# SPI_SensorShield.net
KiCad netlist of a schematic drawn in EAGLE
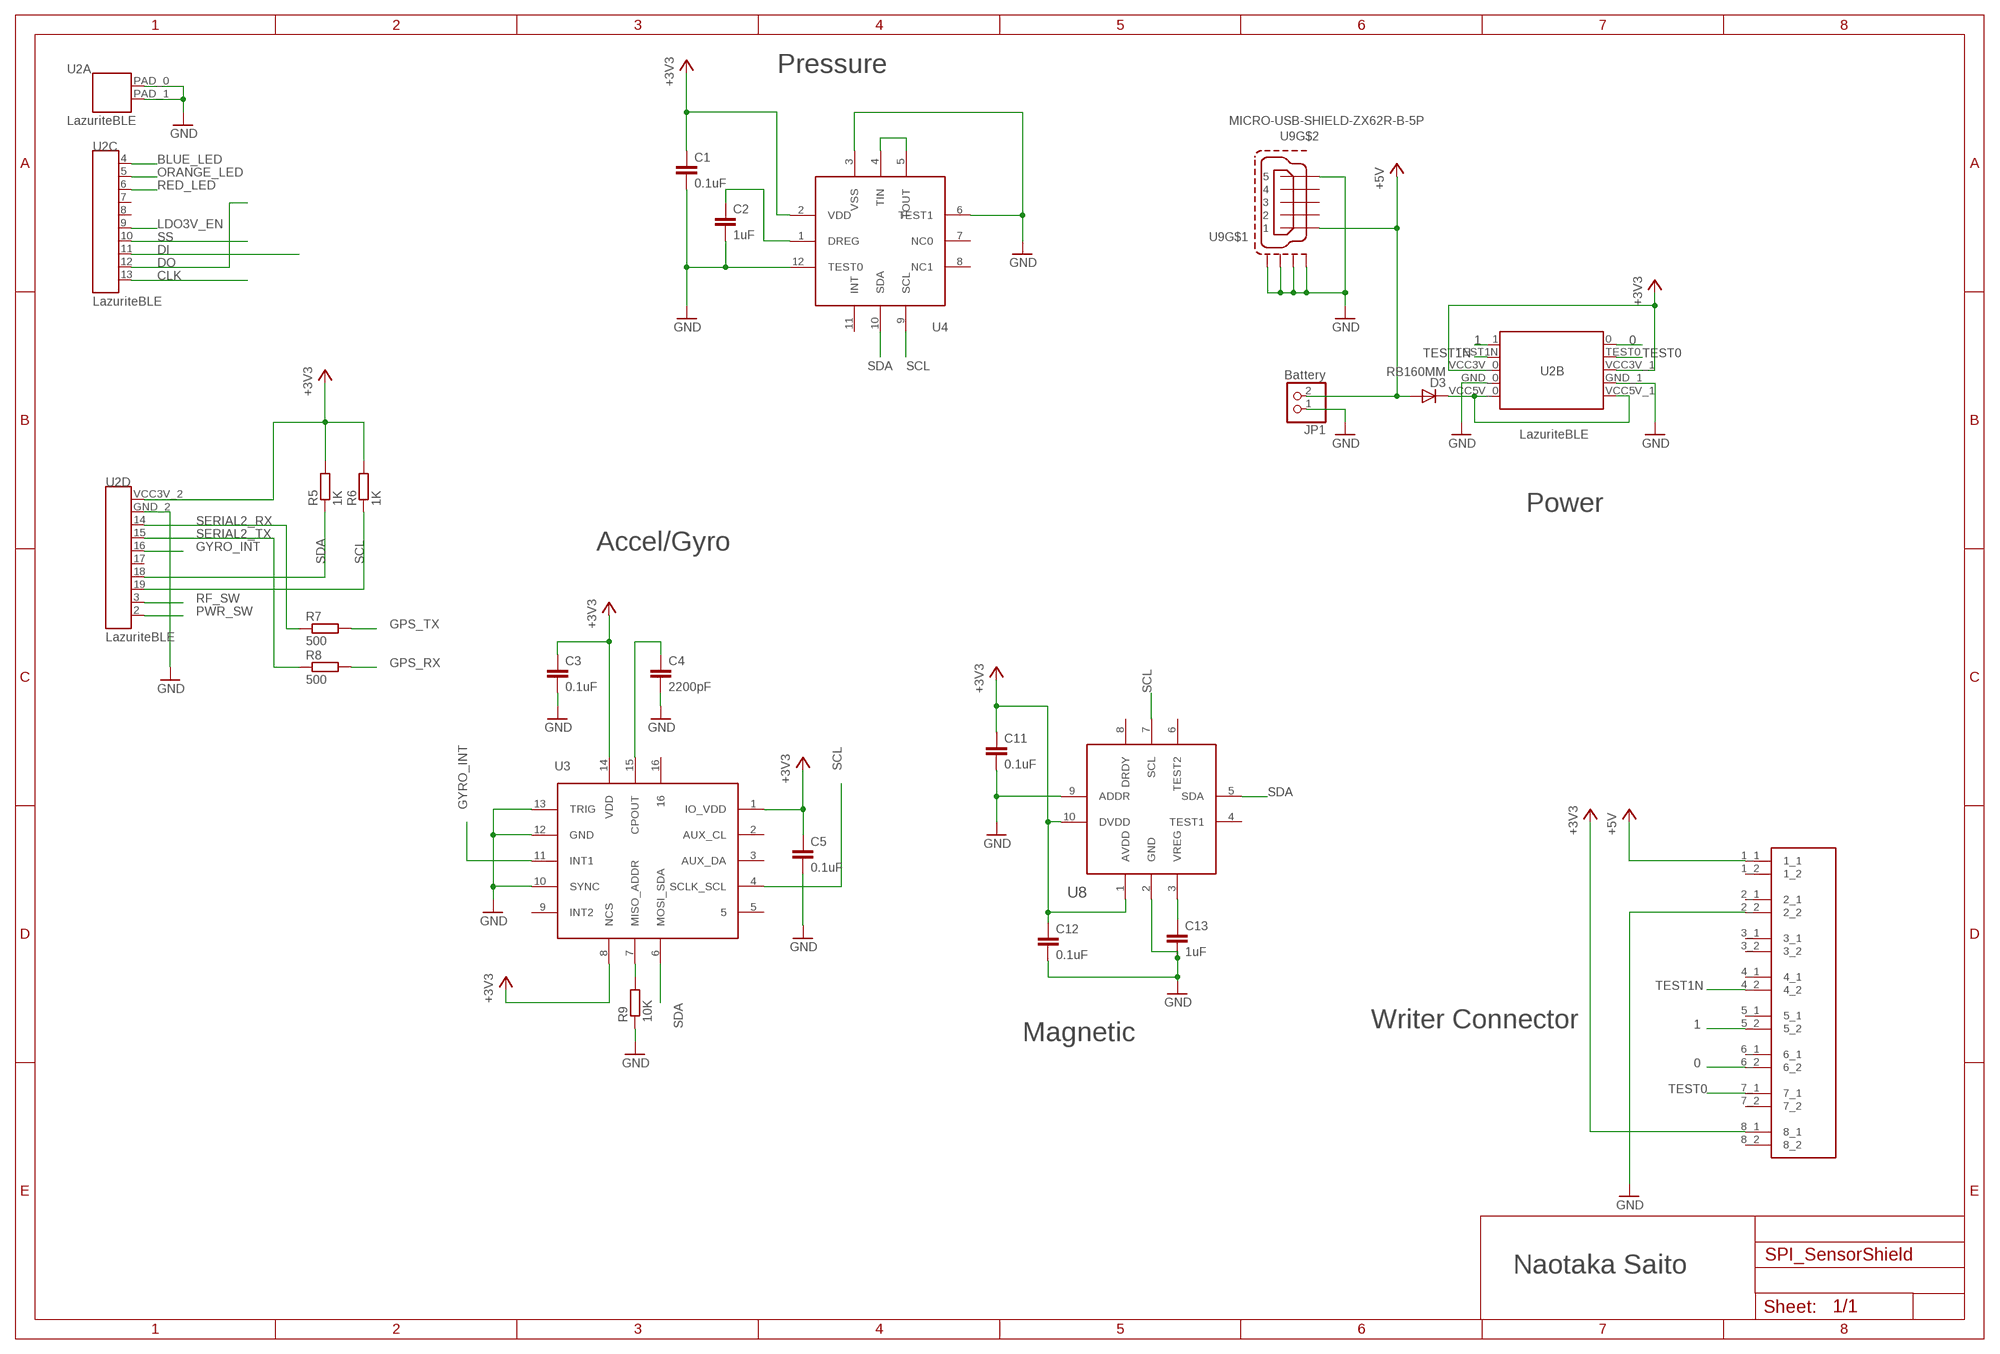
[diagram p0: schematic, sheet 1]

(export (version "E")
  (design (tool "Eeschema 10.0.6"))
  (components
    (comp (ref "C1")
      (value "0.1uF")
      (footprint "eagle-import:C0603")
      (libsource (lib "eagle-import") (part "C-EUC0603"))
    )
    (comp (ref "C2")
      (value "1uF")
      (footprint "eagle-import:C0603")
      (libsource (lib "eagle-import") (part "C-EUC0603"))
    )
    (comp (ref "C3")
      (value "0.1uF")
      (footprint "eagle-import:C0603")
      (libsource (lib "eagle-import") (part "C-EUC0603"))
    )
    (comp (ref "C4")
      (value "2200pF")
      (footprint "eagle-import:C0603")
      (libsource (lib "eagle-import") (part "C-EUC0603"))
    )
    (comp (ref "C5")
      (value "0.1uF")
      (footprint "eagle-import:C0603")
      (libsource (lib "eagle-import") (part "C-EUC0603"))
    )
    (comp (ref "C11")
      (value "0.1uF")
      (footprint "eagle-import:C0603")
      (libsource (lib "eagle-import") (part "C-EUC0603"))
    )
    (comp (ref "C12")
      (value "0.1uF")
      (footprint "eagle-import:C0603")
      (libsource (lib "eagle-import") (part "C-EUC0603"))
    )
    (comp (ref "C13")
      (value "1uF")
      (footprint "eagle-import:C0603")
      (libsource (lib "eagle-import") (part "C-EUC0603"))
    )
    (comp (ref "D3")
      (value "RB160MM")
      (footprint "eagle-import:RB160MM-30")
      (libsource (lib "eagle-import") (part "RB160MM"))
    )
    (comp (ref "JP1")
      (value "Battery")
      (footprint "eagle-import:1X02")
      (libsource (lib "eagle-import") (part "PINHD-1X2"))
    )
    (comp (ref "R5")
      (value "1K")
      (footprint "eagle-import:R0603")
      (libsource (lib "eagle-import") (part "R-EU_R0603"))
    )
    (comp (ref "R6")
      (value "1K")
      (footprint "eagle-import:R0603")
      (libsource (lib "eagle-import") (part "R-EU_R0603"))
    )
    (comp (ref "R7")
      (value "500")
      (footprint "eagle-import:R0603")
      (libsource (lib "eagle-import") (part "R-EU_R0603"))
    )
    (comp (ref "R8")
      (value "500")
      (footprint "eagle-import:R0603")
      (libsource (lib "eagle-import") (part "R-EU_R0603"))
    )
    (comp (ref "R9")
      (value "10K")
      (footprint "eagle-import:R0603")
      (libsource (lib "eagle-import") (part "R-EU_R0603"))
    )
    (comp (ref "U$1")
      (value "XB-1-X")
      (footprint "eagle-import:XB-1-X")
      (libsource (lib "eagle-import") (part "XB-1-X"))
    )
    (comp (ref "U2")
      (value "LazuriteBLE")
      (footprint "eagle-import:LAZURITE920J")
      (libsource (lib "eagle-import") (part "LAZURITE920JLAZURITE920J"))
    )
    (comp (ref "U3")
      (value "KXG03")
      (footprint "eagle-import:KXG03")
      (libsource (lib "eagle-import") (part "KXG03"))
    )
    (comp (ref "U4")
      (value "BM1383AGLV")
      (footprint "eagle-import:BM1383AGLV")
      (libsource (lib "eagle-import") (part "BM1383AGLV"))
    )
    (comp (ref "U8")
      (value "BM1422AGMV")
      (footprint "eagle-import:BM1422AGMV")
      (libsource (lib "eagle-import") (part "BM1422AGMV"))
    )
    (comp (ref "U9")
      (value "MICRO-USB-SHIELD-ZX62R-B-5P")
      (footprint "eagle-import:ZX62R-B-5P")
      (libsource (lib "eagle-import") (part "MICRO-USB-SHIELD-ZX62R-B-5P"))
    )
  )
  (nets
    (net (code "1") (name "+3V3") (class "Default")
      (node (ref "C1") (pin "1") (pinfunction "1_1") (pintype "passive"))
      (node (ref "C11") (pin "1") (pinfunction "1_1") (pintype "passive"))
      (node (ref "C12") (pin "1") (pinfunction "1_1") (pintype "passive"))
      (node (ref "C3") (pin "1") (pinfunction "1_1") (pintype "passive"))
      (node (ref "C5") (pin "1") (pinfunction "1_1") (pintype "passive"))
      (node (ref "R5") (pin "2") (pinfunction "2_2") (pintype "passive"))
      (node (ref "R6") (pin "2") (pinfunction "2_2") (pintype "passive"))
      (node (ref "U$1") (pin "8_1") (pinfunction "8_1_8_1") (pintype "bidirectional"))
      (node (ref "U2") (pin "VCC3V_0") (pinfunction "VCC3V_0_VCC3V_0") (pintype "passive"))
      (node (ref "U2") (pin "VCC3V_1") (pinfunction "VCC3V_1_VCC3V_1") (pintype "passive"))
      (node (ref "U2") (pin "VCC3V_2") (pinfunction "VCC3V_2_VCC3V_2") (pintype "passive"))
      (node (ref "U3") (pin "1") (pinfunction "IO_VDD_1") (pintype "power_in"))
      (node (ref "U3") (pin "14") (pinfunction "VDD_14") (pintype "power_in"))
      (node (ref "U3") (pin "8") (pinfunction "NCS_8") (pintype "bidirectional"))
      (node (ref "U4") (pin "2") (pinfunction "VDD_2") (pintype "power_in"))
      (node (ref "U8") (pin "1") (pinfunction "AVDD_1") (pintype "power_in"))
      (node (ref "U8") (pin "10") (pinfunction "DVDD_10") (pintype "power_in"))
    )
    (net (code "2") (name "+5V") (class "Default")
      (node (ref "D3") (pin "A") (pinfunction "A_A") (pintype "passive"))
      (node (ref "JP1") (pin "2") (pinfunction "2_2") (pintype "passive"))
      (node (ref "U$1") (pin "1_1") (pinfunction "1_1_1_1") (pintype "bidirectional"))
      (node (ref "U9") (pin "1") (pinfunction "1_1") (pintype "input"))
    )
    (net (code "3") (name "/0") (class "Default")
      (node (ref "U$1") (pin "6_2") (pinfunction "6_2_6_2") (pintype "bidirectional"))
      (node (ref "U2") (pin "0") (pinfunction "0_0") (pintype "passive"))
    )
    (net (code "4") (name "/1") (class "Default")
      (node (ref "U$1") (pin "5_2") (pinfunction "5_2_5_2") (pintype "bidirectional"))
      (node (ref "U2") (pin "1") (pinfunction "1_1") (pintype "passive"))
    )
    (net (code "5") (name "/BLUE_LED") (class "Default")
      (node (ref "U2") (pin "4") (pinfunction "4_4") (pintype "passive"))
    )
    (net (code "6") (name "/CLK") (class "Default")
      (node (ref "U2") (pin "13") (pinfunction "13_13") (pintype "passive"))
    )
    (net (code "7") (name "/DI") (class "Default")
      (node (ref "U2") (pin "11") (pinfunction "11_11") (pintype "passive"))
    )
    (net (code "8") (name "/DO") (class "Default")
      (node (ref "U2") (pin "12") (pinfunction "12_12") (pintype "passive"))
    )
    (net (code "9") (name "/GPS_RX") (class "Default")
      (node (ref "R8") (pin "2") (pinfunction "2_2") (pintype "passive"))
    )
    (net (code "10") (name "/GPS_TX") (class "Default")
      (node (ref "R7") (pin "2") (pinfunction "2_2") (pintype "passive"))
    )
    (net (code "11") (name "/GYRO_INT") (class "Default")
      (node (ref "U2") (pin "16") (pinfunction "16_16") (pintype "passive"))
      (node (ref "U3") (pin "11") (pinfunction "INT1_11") (pintype "output"))
    )
    (net (code "12") (name "/LDO3V_EN") (class "Default")
      (node (ref "U2") (pin "9") (pinfunction "9_9") (pintype "passive"))
    )
    (net (code "13") (name "/ORANGE_LED") (class "Default")
      (node (ref "U2") (pin "5") (pinfunction "5_5") (pintype "passive"))
    )
    (net (code "14") (name "/PWR_SW") (class "Default")
      (node (ref "U2") (pin "2") (pinfunction "2_2") (pintype "passive"))
    )
    (net (code "15") (name "/RED_LED") (class "Default")
      (node (ref "U2") (pin "6") (pinfunction "6_6") (pintype "passive"))
    )
    (net (code "16") (name "/RF_SW") (class "Default")
      (node (ref "U2") (pin "3") (pinfunction "3_3") (pintype "passive"))
    )
    (net (code "17") (name "/SCL") (class "Default")
      (node (ref "R6") (pin "1") (pinfunction "1_1") (pintype "passive"))
      (node (ref "U2") (pin "19") (pinfunction "19_19") (pintype "passive"))
      (node (ref "U3") (pin "4") (pinfunction "SCLK_SCL_4") (pintype "input"))
      (node (ref "U4") (pin "9") (pinfunction "SCL_9") (pintype "bidirectional"))
      (node (ref "U8") (pin "7") (pinfunction "SCL_7") (pintype "input"))
    )
    (net (code "18") (name "/SDA") (class "Default")
      (node (ref "R5") (pin "1") (pinfunction "1_1") (pintype "passive"))
      (node (ref "U2") (pin "18") (pinfunction "18_18") (pintype "passive"))
      (node (ref "U3") (pin "6") (pinfunction "MOSI_SDA_6") (pintype "bidirectional"))
      (node (ref "U4") (pin "10") (pinfunction "SDA_10") (pintype "bidirectional"))
      (node (ref "U8") (pin "5") (pinfunction "SDA_5") (pintype "bidirectional"))
    )
    (net (code "19") (name "/SERIAL2_RX") (class "Default")
      (node (ref "R7") (pin "1") (pinfunction "1_1") (pintype "passive"))
      (node (ref "U2") (pin "14") (pinfunction "14_14") (pintype "passive"))
    )
    (net (code "20") (name "/SERIAL2_TX") (class "Default")
      (node (ref "R8") (pin "1") (pinfunction "1_1") (pintype "passive"))
      (node (ref "U2") (pin "15") (pinfunction "15_15") (pintype "passive"))
    )
    (net (code "21") (name "/SS") (class "Default")
      (node (ref "U2") (pin "10") (pinfunction "10_10") (pintype "passive"))
    )
    (net (code "22") (name "/TEST0") (class "Default")
      (node (ref "U$1") (pin "7_1") (pinfunction "7_1_7_1") (pintype "bidirectional"))
      (node (ref "U2") (pin "TEST0") (pinfunction "TEST0_TEST0") (pintype "passive"))
    )
    (net (code "23") (name "/TEST1N") (class "Default")
      (node (ref "U$1") (pin "4_2") (pinfunction "4_2_4_2") (pintype "bidirectional"))
      (node (ref "U2") (pin "TEST1N") (pinfunction "TEST1N_TEST1N") (pintype "passive"))
    )
    (net (code "24") (name "GND") (class "Default")
      (node (ref "C1") (pin "2") (pinfunction "2_2") (pintype "passive"))
      (node (ref "C11") (pin "2") (pinfunction "2_2") (pintype "passive"))
      (node (ref "C12") (pin "2") (pinfunction "2_2") (pintype "passive"))
      (node (ref "C13") (pin "2") (pinfunction "2_2") (pintype "passive"))
      (node (ref "C2") (pin "2") (pinfunction "2_2") (pintype "passive"))
      (node (ref "C3") (pin "2") (pinfunction "2_2") (pintype "passive"))
      (node (ref "C4") (pin "2") (pinfunction "2_2") (pintype "passive"))
      (node (ref "C5") (pin "2") (pinfunction "2_2") (pintype "passive"))
      (node (ref "JP1") (pin "1") (pinfunction "1_1") (pintype "passive"))
      (node (ref "R9") (pin "1") (pinfunction "1_1") (pintype "passive"))
      (node (ref "U$1") (pin "2_2") (pinfunction "2_2_2_2") (pintype "bidirectional"))
      (node (ref "U2") (pin "GND_0") (pinfunction "GND_0_GND_0") (pintype "passive"))
      (node (ref "U2") (pin "GND_1") (pinfunction "GND_1_GND_1") (pintype "passive"))
      (node (ref "U2") (pin "GND_2") (pinfunction "GND_2_GND_2") (pintype "passive"))
      (node (ref "U2") (pin "PAD_0") (pinfunction "PAD_0_PAD_0") (pintype "passive"))
      (node (ref "U2") (pin "PAD_1") (pinfunction "PAD_1_PAD_1") (pintype "passive"))
      (node (ref "U3") (pin "10") (pinfunction "SYNC_10") (pintype "bidirectional"))
      (node (ref "U3") (pin "12") (pinfunction "GND_12") (pintype "power_in"))
      (node (ref "U3") (pin "13") (pinfunction "TRIG_13") (pintype "input"))
      (node (ref "U4") (pin "12") (pinfunction "TEST0_12") (pintype "bidirectional"))
      (node (ref "U4") (pin "3") (pinfunction "VSS_3") (pintype "power_in"))
      (node (ref "U4") (pin "6") (pinfunction "TEST1_6") (pintype "bidirectional"))
      (node (ref "U8") (pin "2") (pinfunction "GND_2") (pintype "power_in"))
      (node (ref "U8") (pin "9") (pinfunction "ADDR_9") (pintype "input"))
      (node (ref "U9") (pin "5") (pinfunction "5_5") (pintype "input"))
      (node (ref "U9") (pin "M1") (pinfunction "S1_M1") (pintype "passive"))
      (node (ref "U9") (pin "M2") (pinfunction "S2_M2") (pintype "passive"))
      (node (ref "U9") (pin "M3") (pinfunction "S3_M3") (pintype "passive"))
      (node (ref "U9") (pin "M4") (pinfunction "S4_M4") (pintype "passive"))
    )
    (net (code "25") (name "Net-(D3-PadC)") (class "Default")
      (node (ref "D3") (pin "C") (pinfunction "C_C") (pintype "passive"))
      (node (ref "U2") (pin "VCC5V_0") (pinfunction "VCC5V_0_VCC5V_0") (pintype "passive"))
      (node (ref "U2") (pin "VCC5V_1") (pinfunction "VCC5V_1_VCC5V_1") (pintype "passive"))
    )
    (net (code "26") (name "Net-(U3-CPOUT)") (class "Default")
      (node (ref "C4") (pin "1") (pinfunction "1_1") (pintype "passive"))
      (node (ref "U3") (pin "15") (pinfunction "CPOUT_15") (pintype "bidirectional"))
    )
    (net (code "27") (name "Net-(U3-MISO_ADDR)") (class "Default")
      (node (ref "R9") (pin "2") (pinfunction "2_2") (pintype "passive"))
      (node (ref "U3") (pin "7") (pinfunction "MISO_ADDR_7") (pintype "bidirectional"))
    )
    (net (code "28") (name "Net-(U4-DREG)") (class "Default")
      (node (ref "C2") (pin "1") (pinfunction "1_1") (pintype "passive"))
      (node (ref "U4") (pin "1") (pinfunction "DREG_1") (pintype "bidirectional"))
    )
    (net (code "29") (name "Net-(U4-TIN)") (class "Default")
      (node (ref "U4") (pin "4") (pinfunction "TIN_4") (pintype "input"))
      (node (ref "U4") (pin "5") (pinfunction "TOUT_5") (pintype "output"))
    )
    (net (code "30") (name "Net-(U8-VREG)") (class "Default")
      (node (ref "C13") (pin "1") (pinfunction "1_1") (pintype "passive"))
      (node (ref "U8") (pin "3") (pinfunction "VREG_3") (pintype "output"))
    )
    (net (code "31") (name "unconnected-(U$1-Pad1_2)") (class "Default")
      (node (ref "U$1") (pin "1_2") (pinfunction "1_2_1_2") (pintype "bidirectional"))
    )
    (net (code "32") (name "unconnected-(U$1-Pad2_1)") (class "Default")
      (node (ref "U$1") (pin "2_1") (pinfunction "2_1_2_1") (pintype "bidirectional"))
    )
    (net (code "33") (name "unconnected-(U$1-Pad3_1)") (class "Default")
      (node (ref "U$1") (pin "3_1") (pinfunction "3_1_3_1") (pintype "bidirectional"))
    )
    (net (code "34") (name "unconnected-(U$1-Pad3_2)") (class "Default")
      (node (ref "U$1") (pin "3_2") (pinfunction "3_2_3_2") (pintype "bidirectional"))
    )
    (net (code "35") (name "unconnected-(U$1-Pad4_1)") (class "Default")
      (node (ref "U$1") (pin "4_1") (pinfunction "4_1_4_1") (pintype "bidirectional"))
    )
    (net (code "36") (name "unconnected-(U$1-Pad5_1)") (class "Default")
      (node (ref "U$1") (pin "5_1") (pinfunction "5_1_5_1") (pintype "bidirectional"))
    )
    (net (code "37") (name "unconnected-(U$1-Pad6_1)") (class "Default")
      (node (ref "U$1") (pin "6_1") (pinfunction "6_1_6_1") (pintype "bidirectional"))
    )
    (net (code "38") (name "unconnected-(U$1-Pad7_2)") (class "Default")
      (node (ref "U$1") (pin "7_2") (pinfunction "7_2_7_2") (pintype "bidirectional"))
    )
    (net (code "39") (name "unconnected-(U$1-Pad8_2)") (class "Default")
      (node (ref "U$1") (pin "8_2") (pinfunction "8_2_8_2") (pintype "bidirectional"))
    )
    (net (code "40") (name "unconnected-(U2-Pad7)") (class "Default")
      (node (ref "U2") (pin "7") (pinfunction "7_7") (pintype "passive"))
    )
    (net (code "41") (name "unconnected-(U2-Pad8)") (class "Default")
      (node (ref "U2") (pin "8") (pinfunction "8_8") (pintype "passive"))
    )
    (net (code "42") (name "unconnected-(U2-Pad17)") (class "Default")
      (node (ref "U2") (pin "17") (pinfunction "17_17") (pintype "passive"))
    )
    (net (code "43") (name "unconnected-(U3-AUX_CL-Pad2)") (class "Default")
      (node (ref "U3") (pin "2") (pinfunction "AUX_CL_2") (pintype "input"))
    )
    (net (code "44") (name "unconnected-(U3-AUX_DA-Pad3)") (class "Default")
      (node (ref "U3") (pin "3") (pinfunction "AUX_DA_3") (pintype "bidirectional"))
    )
    (net (code "45") (name "unconnected-(U3-INT2-Pad9)") (class "Default")
      (node (ref "U3") (pin "9") (pinfunction "INT2_9") (pintype "output"))
    )
    (net (code "46") (name "unconnected-(U3-Pad5)") (class "Default")
      (node (ref "U3") (pin "5") (pinfunction "5_5") (pintype "no_connect"))
    )
    (net (code "47") (name "unconnected-(U3-Pad16)") (class "Default")
      (node (ref "U3") (pin "16") (pinfunction "16_16") (pintype "no_connect"))
    )
    (net (code "48") (name "unconnected-(U4-INT-Pad11)") (class "Default")
      (node (ref "U4") (pin "11") (pinfunction "INT_11") (pintype "output"))
    )
    (net (code "49") (name "unconnected-(U4-NC0-Pad7)") (class "Default")
      (node (ref "U4") (pin "7") (pinfunction "NC0_7") (pintype "no_connect"))
    )
    (net (code "50") (name "unconnected-(U4-NC1-Pad8)") (class "Default")
      (node (ref "U4") (pin "8") (pinfunction "NC1_8") (pintype "no_connect"))
    )
    (net (code "51") (name "unconnected-(U8-DRDY-Pad8)") (class "Default")
      (node (ref "U8") (pin "8") (pinfunction "DRDY_8") (pintype "output"))
    )
    (net (code "52") (name "unconnected-(U8-TEST1-Pad4)") (class "Default")
      (node (ref "U8") (pin "4") (pinfunction "TEST1_4") (pintype "no_connect"))
    )
    (net (code "53") (name "unconnected-(U8-TEST2-Pad6)") (class "Default")
      (node (ref "U8") (pin "6") (pinfunction "TEST2_6") (pintype "no_connect"))
    )
    (net (code "54") (name "unconnected-(U9-Pad2)") (class "Default")
      (node (ref "U9") (pin "2") (pinfunction "2_2") (pintype "input"))
    )
    (net (code "55") (name "unconnected-(U9-Pad3)") (class "Default")
      (node (ref "U9") (pin "3") (pinfunction "3_3") (pintype "input"))
    )
    (net (code "56") (name "unconnected-(U9-Pad4)") (class "Default")
      (node (ref "U9") (pin "4") (pinfunction "4_4") (pintype "input"))
    )
  )
)
